# MCU_v14.net
KiCad netlist of a schematic drawn in EAGLE
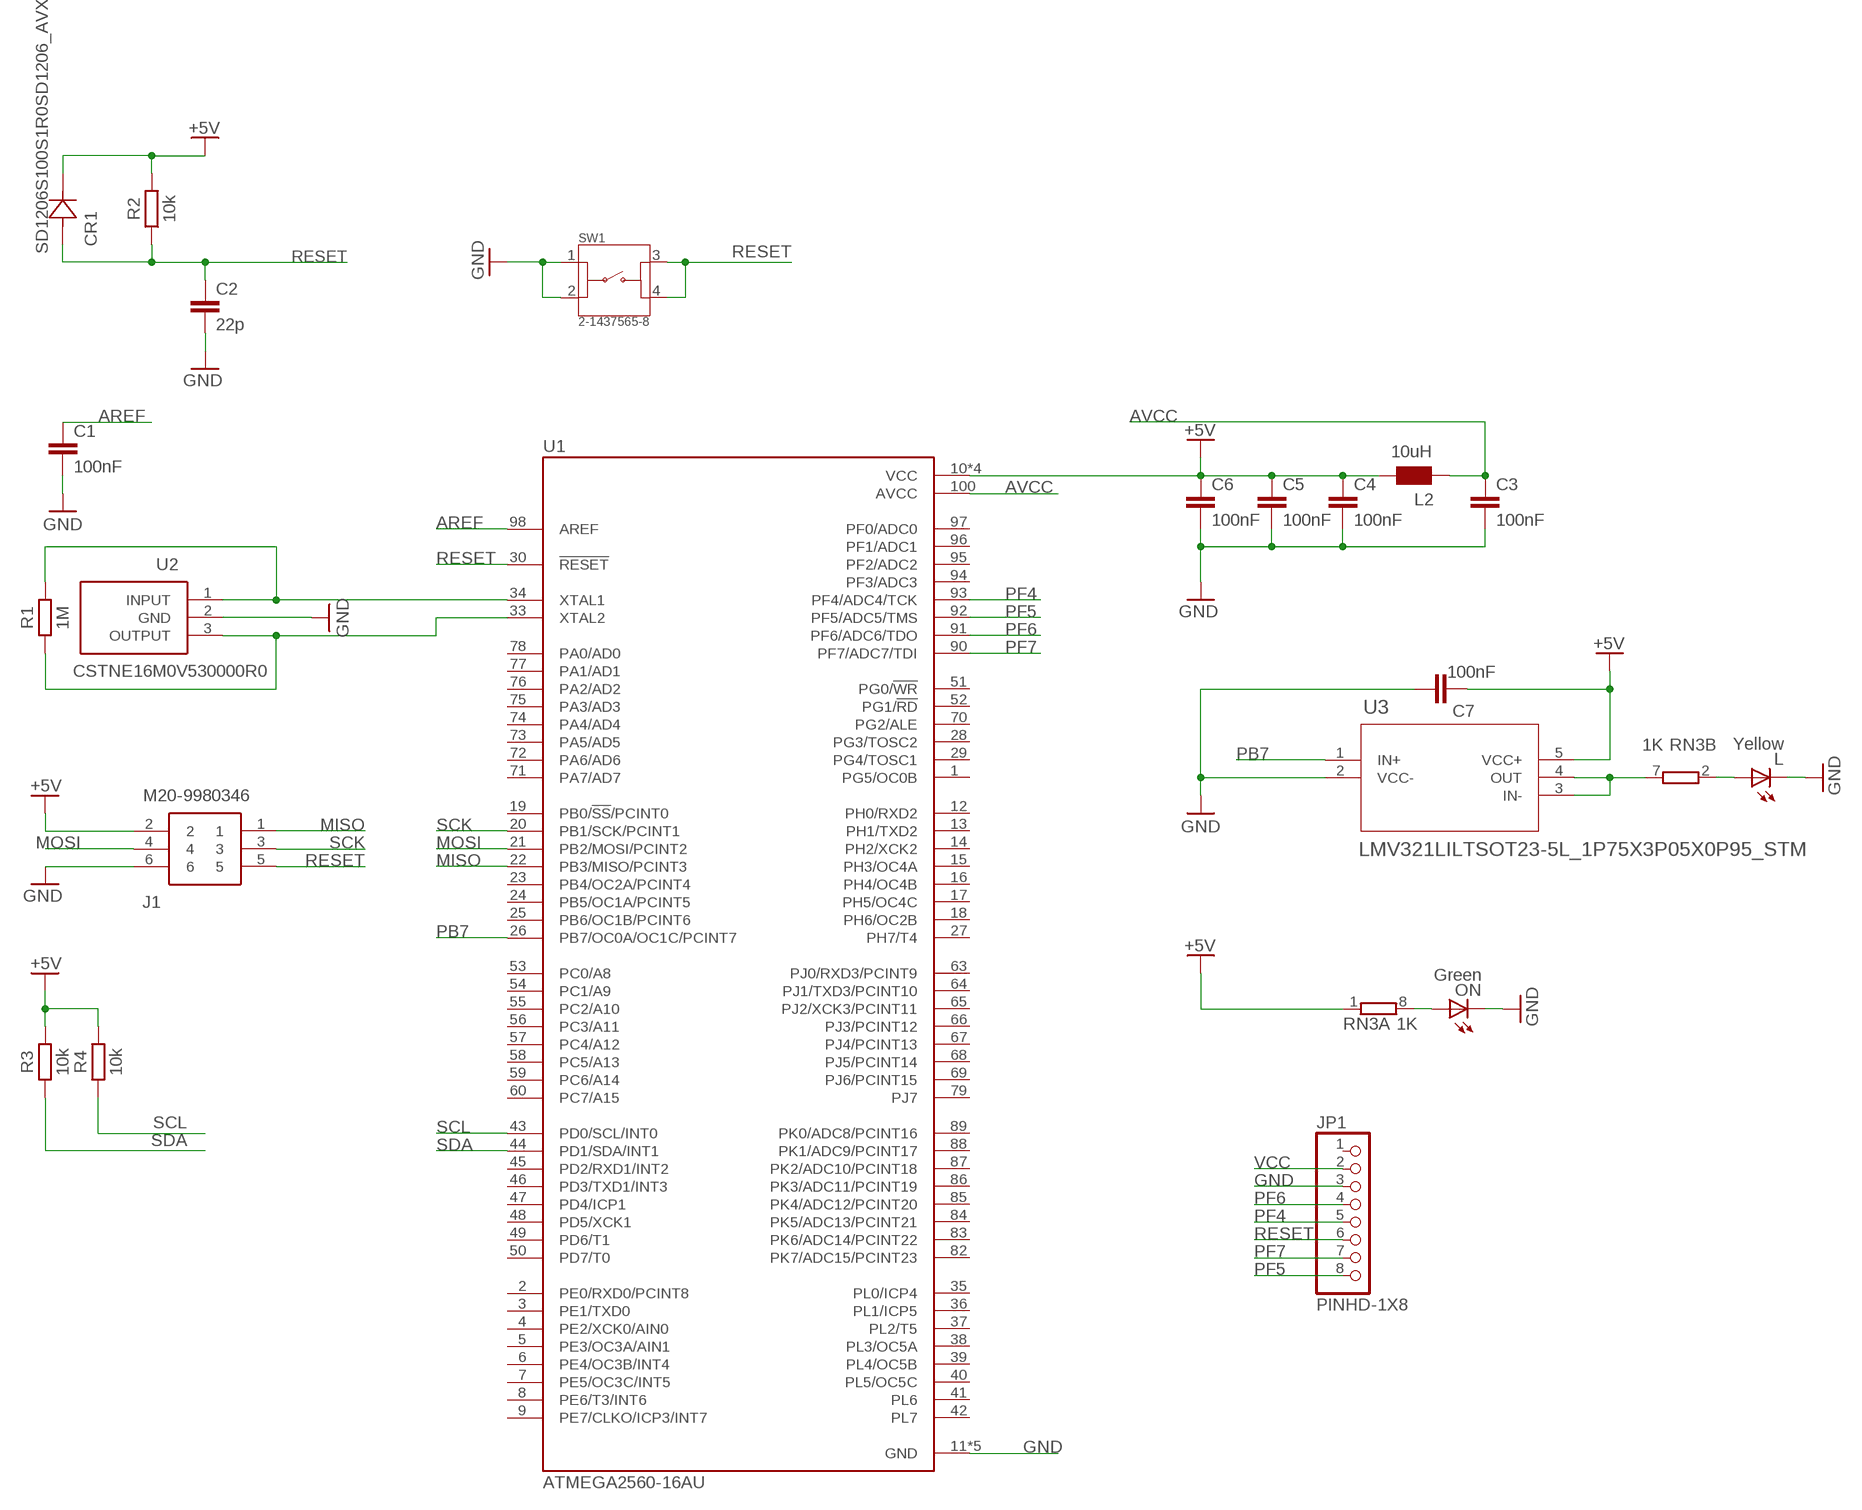
[diagram p0: schematic, sheet 1]

(export (version "E")
  (design (tool "Eeschema 10.0.6"))
  (components
    (comp (ref "C1")
      (value "100nF")
      (footprint "eagle-import:C0603-ROUND")
      (fields (field (name "PART_NUMBER") "cl10b104kbnc"))
      (libsource (lib "eagle-import") (part "0015_100NF_0603"))
    )
    (comp (ref "C2")
      (value "22p")
      (footprint "eagle-import:C0603-ROUND")
      (fields (field (name "PART_NUMBER") "22pF_0603"))
      (libsource (lib "eagle-import") (part "0014_22PF_0603"))
    )
    (comp (ref "C3")
      (value "100nF")
      (footprint "eagle-import:C0603-ROUND")
      (fields (field (name "PART_NUMBER") "cl10b104kbnc"))
      (libsource (lib "eagle-import") (part "0015_100NF_0603"))
    )
    (comp (ref "C4")
      (value "100nF")
      (footprint "eagle-import:C0603-ROUND")
      (fields (field (name "PART_NUMBER") "cl10b104kbnc"))
      (libsource (lib "eagle-import") (part "0015_100NF_0603"))
    )
    (comp (ref "C5")
      (value "100nF")
      (footprint "eagle-import:C0603-ROUND")
      (fields (field (name "PART_NUMBER") "cl10b104kbnc"))
      (libsource (lib "eagle-import") (part "0015_100NF_0603"))
    )
    (comp (ref "C6")
      (value "100nF")
      (footprint "eagle-import:C0603-ROUND")
      (fields (field (name "PART_NUMBER") "cl10b104kbnc"))
      (libsource (lib "eagle-import") (part "0015_100NF_0603"))
    )
    (comp (ref "C7")
      (value "100nF")
      (footprint "eagle-import:C0603-ROUND")
      (fields (field (name "PART_NUMBER") "cl10b104kbnc"))
      (libsource (lib "eagle-import") (part "0015_100NF_0603"))
    )
    (comp (ref "CR1")
      (value "SD1206S100S1R0SD1206_AVX")
      (footprint "eagle-import:SD1206_AVX")
      (fields
        (field (name "MANUFACTURER_PART_NUMBER") "SD1206S100S1R0")
        (field (name "COPYRIGHT") "Copyright (C) 2024 Ultra Librarian. All rights reserved.")
      )
      (libsource (lib "eagle-import") (part "SD1206S100S1R0SD1206_AVX"))
    )
    (comp (ref "J1")
      (value "M20-9980346")
      (footprint "eagle-import:HDRV6W64P254_2X3_762X508X868P")
      (fields (field (name "MOUSER_PART_NUMBER") "855-M20-9980346"))
      (libsource (lib "eagle-import") (part "M20-9980346"))
    )
    (comp (ref "JP1")
      (value "PINHD-1X8")
      (footprint "eagle-import:1X08")
      (fields (field (name "MANUFACTURER") "Generic"))
      (libsource (lib "eagle-import") (part "PINHD-1X8"))
    )
    (comp (ref "L")
      (value "Yellow")
      (footprint "eagle-import:CHIPLED_0805")
      (fields (field (name "PART_NUMBER") "KPT-2012YC"))
      (libsource (lib "eagle-import") (part "0044_KPT-2012YC"))
    )
    (comp (ref "L2")
      (value "10uH")
      (footprint "eagle-import:0805")
      (fields (field (name "PART_NUMBER") "CV201210-100K"))
      (libsource (lib "eagle-import") (part "0715_CV201210-100K"))
    )
    (comp (ref "ON")
      (value "Green")
      (footprint "eagle-import:CHIPLED_0805")
      (fields (field (name "PART_NUMBER") "KPT-2012SGC"))
      (libsource (lib "eagle-import") (part "0043_KPT-2012SGC"))
    )
    (comp (ref "R1")
      (value "1M")
      (footprint "eagle-import:RESC1608X60")
      (libsource (lib "eagle-import") (part "RCHIP-0603(1608-METRIC)_"))
    )
    (comp (ref "R2")
      (value "10k")
      (footprint "eagle-import:RESC2012X65")
      (libsource (lib "eagle-import") (part "RCHIP-0805(2012-METRIC)_"))
    )
    (comp (ref "R3")
      (value "10k")
      (footprint "eagle-import:RESC2012X65")
      (libsource (lib "eagle-import") (part "RCHIP-0805(2012-METRIC)_"))
    )
    (comp (ref "R4")
      (value "10k")
      (footprint "eagle-import:RESC2012X65")
      (libsource (lib "eagle-import") (part "RCHIP-0805(2012-METRIC)_"))
    )
    (comp (ref "RN3")
      (value "1K")
      (footprint "eagle-import:CAY16")
      (fields (field (name "PART_NUMBER") "064R_1K_/_CAY16-102J4LF"))
      (libsource (lib "eagle-import") (part "0005_064R_1K_/_CAY16-102J4LF"))
    )
    (comp (ref "SW1")
      (value "2-1437565-8")
      (footprint "eagle-import:SW_SMD_2-1437565-8_4_4.50_6.00_6.00_5.00")
      (fields (field (name "MANUFACTURER") "TE connectivity"))
      (libsource (lib "eagle-import") (part "2-1437565-8"))
    )
    (comp (ref "U1")
      (value "ATMEGA2560-16AU")
      (footprint "eagle-import:QFP50P1600X1600X120-100N")
      (fields (field (name "MANUFACTURER") "Microchip Technology"))
      (libsource (lib "eagle-import") (part "ATMEGA2560-16AU"))
    )
    (comp (ref "U2")
      (value "CSTNE16M0V530000R0")
      (footprint "eagle-import:CSTNE16M0V530000R0")
      (fields (field (name "MOUSER_PART_NUMBER") "81-CSTNE16M0V530000R"))
      (libsource (lib "eagle-import") (part "CSTNE16M0V530000R0"))
    )
    (comp (ref "U3")
      (value "LMV321LILTSOT23-5L_1P75X3P05X0P95_STM")
      (footprint "eagle-import:SOT23-5L_1P75X3P05X0P95_STM")
      (fields
        (field (name "MANUFACTURER_PART_NUMBER") "LMV321LILT")
        (field (name "COPYRIGHT") "Copyright (C) 2024 Ultra Librarian. All rights reserved.")
      )
      (libsource (lib "eagle-import") (part "LMV321LILTSOT23-5L_1P75X3P05X0P95_STM"))
    )
  )
  (nets
    (net (code "1") (name "+5V") (class "Default")
      (node (ref "C4") (pin "1") (pinfunction "1_1") (pintype "passive"))
      (node (ref "C5") (pin "1") (pinfunction "1_1") (pintype "passive"))
      (node (ref "C6") (pin "1") (pinfunction "1_1") (pintype "passive"))
      (node (ref "C7") (pin "1") (pinfunction "1_1") (pintype "passive"))
      (node (ref "CR1") (pin "1") (pinfunction "1_1") (pintype "passive"))
      (node (ref "J1") (pin "2") (pinfunction "2_2") (pintype "bidirectional"))
      (node (ref "L2") (pin "2") (pinfunction "2_2") (pintype "passive"))
      (node (ref "R2") (pin "2") (pinfunction "2_2") (pintype "passive"))
      (node (ref "R3") (pin "2") (pinfunction "2_2") (pintype "passive"))
      (node (ref "R4") (pin "2") (pinfunction "2_2") (pintype "passive"))
      (node (ref "RN3") (pin "1") (pinfunction "1_1") (pintype "passive"))
      (node (ref "U1") (pin "10") (pinfunction "VCC_10") (pintype "power_in"))
      (node (ref "U1") (pin "31") (pinfunction "VCC_31") (pintype "power_in"))
      (node (ref "U1") (pin "61") (pinfunction "VCC_61") (pintype "power_in"))
      (node (ref "U1") (pin "80") (pinfunction "VCC_80") (pintype "power_in"))
      (node (ref "U3") (pin "5") (pinfunction "VCC+_5") (pintype "power_in"))
    )
    (net (code "2") (name "/AREF") (class "Default")
      (node (ref "C1") (pin "1") (pinfunction "1_1") (pintype "passive"))
      (node (ref "U1") (pin "98") (pinfunction "AREF_98") (pintype "input"))
    )
    (net (code "3") (name "/AVCC") (class "Default")
      (node (ref "C3") (pin "1") (pinfunction "1_1") (pintype "passive"))
      (node (ref "L2") (pin "1") (pinfunction "1_1") (pintype "passive"))
      (node (ref "U1") (pin "100") (pinfunction "AVCC_100") (pintype "power_in"))
    )
    (net (code "4") (name "/MISO") (class "Default")
      (node (ref "J1") (pin "1") (pinfunction "1_1") (pintype "bidirectional"))
      (node (ref "U1") (pin "22") (pinfunction "PB3/MISO/PCINT3_22") (pintype "bidirectional"))
    )
    (net (code "5") (name "/MOSI") (class "Default")
      (node (ref "J1") (pin "4") (pinfunction "4_4") (pintype "bidirectional"))
      (node (ref "U1") (pin "21") (pinfunction "PB2/MOSI/PCINT2_21") (pintype "bidirectional"))
    )
    (net (code "6") (name "/PB7") (class "Default")
      (node (ref "U1") (pin "26") (pinfunction "PB7/OC0A/OC1C/PCINT7_26") (pintype "bidirectional"))
      (node (ref "U3") (pin "1") (pinfunction "IN+_1") (pintype "input"))
    )
    (net (code "7") (name "/PF4") (class "Default")
      (node (ref "JP1") (pin "5") (pinfunction "5_5") (pintype "passive"))
      (node (ref "U1") (pin "93") (pinfunction "PF4/ADC4/TCK_93") (pintype "bidirectional"))
    )
    (net (code "8") (name "/PF5") (class "Default")
      (node (ref "JP1") (pin "8") (pinfunction "8_8") (pintype "passive"))
      (node (ref "U1") (pin "92") (pinfunction "PF5/ADC5/TMS_92") (pintype "bidirectional"))
    )
    (net (code "9") (name "/PF6") (class "Default")
      (node (ref "JP1") (pin "4") (pinfunction "4_4") (pintype "passive"))
      (node (ref "U1") (pin "91") (pinfunction "PF6/ADC6/TDO_91") (pintype "bidirectional"))
    )
    (net (code "10") (name "/PF7") (class "Default")
      (node (ref "JP1") (pin "7") (pinfunction "7_7") (pintype "passive"))
      (node (ref "U1") (pin "90") (pinfunction "PF7/ADC7/TDI_90") (pintype "bidirectional"))
    )
    (net (code "11") (name "/RESET") (class "Default")
      (node (ref "C2") (pin "1") (pinfunction "1_1") (pintype "passive"))
      (node (ref "CR1") (pin "2") (pinfunction "2_2") (pintype "passive"))
      (node (ref "J1") (pin "5") (pinfunction "5_5") (pintype "bidirectional"))
      (node (ref "JP1") (pin "6") (pinfunction "6_6") (pintype "passive"))
      (node (ref "R2") (pin "1") (pinfunction "1_1") (pintype "passive"))
      (node (ref "SW1") (pin "3") (pinfunction "3_3") (pintype "passive"))
      (node (ref "SW1") (pin "4") (pinfunction "4_4") (pintype "passive"))
      (node (ref "U1") (pin "30") (pinfunction "~{RESET}_30") (pintype "input"))
    )
    (net (code "12") (name "/SCK") (class "Default")
      (node (ref "J1") (pin "3") (pinfunction "3_3") (pintype "bidirectional"))
      (node (ref "U1") (pin "20") (pinfunction "PB1/SCK/PCINT1_20") (pintype "bidirectional"))
    )
    (net (code "13") (name "/SCL") (class "Default")
      (node (ref "R4") (pin "1") (pinfunction "1_1") (pintype "passive"))
      (node (ref "U1") (pin "43") (pinfunction "PD0/SCL/INT0_43") (pintype "bidirectional"))
    )
    (net (code "14") (name "/SDA") (class "Default")
      (node (ref "R3") (pin "1") (pinfunction "1_1") (pintype "passive"))
      (node (ref "U1") (pin "44") (pinfunction "PD1/SDA/INT1_44") (pintype "bidirectional"))
    )
    (net (code "15") (name "/VCC") (class "Default")
      (node (ref "JP1") (pin "2") (pinfunction "2_2") (pintype "passive"))
    )
    (net (code "16") (name "GND") (class "Default")
      (node (ref "C1") (pin "2") (pinfunction "2_2") (pintype "passive"))
      (node (ref "C2") (pin "2") (pinfunction "2_2") (pintype "passive"))
      (node (ref "C3") (pin "2") (pinfunction "2_2") (pintype "passive"))
      (node (ref "C4") (pin "2") (pinfunction "2_2") (pintype "passive"))
      (node (ref "C5") (pin "2") (pinfunction "2_2") (pintype "passive"))
      (node (ref "C6") (pin "2") (pinfunction "2_2") (pintype "passive"))
      (node (ref "C7") (pin "2") (pinfunction "2_2") (pintype "passive"))
      (node (ref "J1") (pin "6") (pinfunction "6_6") (pintype "bidirectional"))
      (node (ref "JP1") (pin "3") (pinfunction "3_3") (pintype "passive"))
      (node (ref "L") (pin "C") (pinfunction "C_C") (pintype "passive"))
      (node (ref "ON") (pin "C") (pinfunction "C_C") (pintype "passive"))
      (node (ref "SW1") (pin "1") (pinfunction "1_1") (pintype "passive"))
      (node (ref "SW1") (pin "2") (pinfunction "2_2") (pintype "passive"))
      (node (ref "U1") (pin "11") (pinfunction "GND_11") (pintype "power_in"))
      (node (ref "U1") (pin "32") (pinfunction "GND_32") (pintype "power_in"))
      (node (ref "U1") (pin "62") (pinfunction "GND_62") (pintype "power_in"))
      (node (ref "U1") (pin "81") (pinfunction "GND_81") (pintype "power_in"))
      (node (ref "U1") (pin "99") (pinfunction "GND_99") (pintype "power_in"))
      (node (ref "U2") (pin "2") (pinfunction "GND_2") (pintype "bidirectional"))
      (node (ref "U3") (pin "2") (pinfunction "VCC-_2") (pintype "power_in"))
    )
    (net (code "17") (name "Net-(RN3A-2)") (class "Default")
      (node (ref "ON") (pin "A") (pinfunction "A_A") (pintype "passive"))
      (node (ref "RN3") (pin "8") (pinfunction "2_8") (pintype "passive"))
    )
    (net (code "18") (name "Net-(RN3B-1)") (class "Default")
      (node (ref "L") (pin "A") (pinfunction "A_A") (pintype "passive"))
      (node (ref "RN3") (pin "2") (pinfunction "1_2") (pintype "passive"))
    )
    (net (code "19") (name "Net-(RN3B-2)") (class "Default")
      (node (ref "RN3") (pin "7") (pinfunction "2_7") (pintype "passive"))
      (node (ref "U3") (pin "3") (pinfunction "IN-_3") (pintype "input"))
      (node (ref "U3") (pin "4") (pinfunction "OUT_4") (pintype "output"))
    )
    (net (code "20") (name "Net-(U1-XTAL1)") (class "Default")
      (node (ref "R1") (pin "2") (pinfunction "2_2") (pintype "passive"))
      (node (ref "U1") (pin "34") (pinfunction "XTAL1_34") (pintype "input"))
      (node (ref "U2") (pin "1") (pinfunction "INPUT_1") (pintype "bidirectional"))
    )
    (net (code "21") (name "Net-(U1-XTAL2)") (class "Default")
      (node (ref "R1") (pin "1") (pinfunction "1_1") (pintype "passive"))
      (node (ref "U1") (pin "33") (pinfunction "XTAL2_33") (pintype "output"))
      (node (ref "U2") (pin "3") (pinfunction "OUTPUT_3") (pintype "bidirectional"))
    )
    (net (code "22") (name "unconnected-(JP1-Pad1)") (class "Default")
      (node (ref "JP1") (pin "1") (pinfunction "1_1") (pintype "passive"))
    )
    (net (code "23") (name "unconnected-(U1-PA0{slash}AD0-Pad78)") (class "Default")
      (node (ref "U1") (pin "78") (pinfunction "PA0/AD0_78") (pintype "bidirectional"))
    )
    (net (code "24") (name "unconnected-(U1-PA1{slash}AD1-Pad77)") (class "Default")
      (node (ref "U1") (pin "77") (pinfunction "PA1/AD1_77") (pintype "bidirectional"))
    )
    (net (code "25") (name "unconnected-(U1-PA2{slash}AD2-Pad76)") (class "Default")
      (node (ref "U1") (pin "76") (pinfunction "PA2/AD2_76") (pintype "bidirectional"))
    )
    (net (code "26") (name "unconnected-(U1-PA3{slash}AD3-Pad75)") (class "Default")
      (node (ref "U1") (pin "75") (pinfunction "PA3/AD3_75") (pintype "bidirectional"))
    )
    (net (code "27") (name "unconnected-(U1-PA4{slash}AD4-Pad74)") (class "Default")
      (node (ref "U1") (pin "74") (pinfunction "PA4/AD4_74") (pintype "bidirectional"))
    )
    (net (code "28") (name "unconnected-(U1-PA5{slash}AD5-Pad73)") (class "Default")
      (node (ref "U1") (pin "73") (pinfunction "PA5/AD5_73") (pintype "bidirectional"))
    )
    (net (code "29") (name "unconnected-(U1-PA6{slash}AD6-Pad72)") (class "Default")
      (node (ref "U1") (pin "72") (pinfunction "PA6/AD6_72") (pintype "bidirectional"))
    )
    (net (code "30") (name "unconnected-(U1-PA7{slash}AD7-Pad71)") (class "Default")
      (node (ref "U1") (pin "71") (pinfunction "PA7/AD7_71") (pintype "bidirectional"))
    )
    (net (code "31") (name "unconnected-(U1-PB0{slash}~{SS}{slash}PCINT0-Pad19)") (class "Default")
      (node (ref "U1") (pin "19") (pinfunction "PB0/~{SS}/PCINT0_19") (pintype "bidirectional"))
    )
    (net (code "32") (name "unconnected-(U1-PB4{slash}OC2A{slash}PCINT4-Pad23)") (class "Default")
      (node (ref "U1") (pin "23") (pinfunction "PB4/OC2A/PCINT4_23") (pintype "bidirectional"))
    )
    (net (code "33") (name "unconnected-(U1-PB5{slash}OC1A{slash}PCINT5-Pad24)") (class "Default")
      (node (ref "U1") (pin "24") (pinfunction "PB5/OC1A/PCINT5_24") (pintype "bidirectional"))
    )
    (net (code "34") (name "unconnected-(U1-PB6{slash}OC1B{slash}PCINT6-Pad25)") (class "Default")
      (node (ref "U1") (pin "25") (pinfunction "PB6/OC1B/PCINT6_25") (pintype "bidirectional"))
    )
    (net (code "35") (name "unconnected-(U1-PC0{slash}A8-Pad53)") (class "Default")
      (node (ref "U1") (pin "53") (pinfunction "PC0/A8_53") (pintype "bidirectional"))
    )
    (net (code "36") (name "unconnected-(U1-PC1{slash}A9-Pad54)") (class "Default")
      (node (ref "U1") (pin "54") (pinfunction "PC1/A9_54") (pintype "bidirectional"))
    )
    (net (code "37") (name "unconnected-(U1-PC2{slash}A10-Pad55)") (class "Default")
      (node (ref "U1") (pin "55") (pinfunction "PC2/A10_55") (pintype "bidirectional"))
    )
    (net (code "38") (name "unconnected-(U1-PC3{slash}A11-Pad56)") (class "Default")
      (node (ref "U1") (pin "56") (pinfunction "PC3/A11_56") (pintype "bidirectional"))
    )
    (net (code "39") (name "unconnected-(U1-PC4{slash}A12-Pad57)") (class "Default")
      (node (ref "U1") (pin "57") (pinfunction "PC4/A12_57") (pintype "bidirectional"))
    )
    (net (code "40") (name "unconnected-(U1-PC5{slash}A13-Pad58)") (class "Default")
      (node (ref "U1") (pin "58") (pinfunction "PC5/A13_58") (pintype "bidirectional"))
    )
    (net (code "41") (name "unconnected-(U1-PC6{slash}A14-Pad59)") (class "Default")
      (node (ref "U1") (pin "59") (pinfunction "PC6/A14_59") (pintype "bidirectional"))
    )
    (net (code "42") (name "unconnected-(U1-PC7{slash}A15-Pad60)") (class "Default")
      (node (ref "U1") (pin "60") (pinfunction "PC7/A15_60") (pintype "bidirectional"))
    )
    (net (code "43") (name "unconnected-(U1-PD2{slash}RXD1{slash}INT2-Pad45)") (class "Default")
      (node (ref "U1") (pin "45") (pinfunction "PD2/RXD1/INT2_45") (pintype "bidirectional"))
    )
    (net (code "44") (name "unconnected-(U1-PD3{slash}TXD1{slash}INT3-Pad46)") (class "Default")
      (node (ref "U1") (pin "46") (pinfunction "PD3/TXD1/INT3_46") (pintype "bidirectional"))
    )
    (net (code "45") (name "unconnected-(U1-PD4{slash}ICP1-Pad47)") (class "Default")
      (node (ref "U1") (pin "47") (pinfunction "PD4/ICP1_47") (pintype "bidirectional"))
    )
    (net (code "46") (name "unconnected-(U1-PD5{slash}XCK1-Pad48)") (class "Default")
      (node (ref "U1") (pin "48") (pinfunction "PD5/XCK1_48") (pintype "bidirectional"))
    )
    (net (code "47") (name "unconnected-(U1-PD6{slash}T1-Pad49)") (class "Default")
      (node (ref "U1") (pin "49") (pinfunction "PD6/T1_49") (pintype "bidirectional"))
    )
    (net (code "48") (name "unconnected-(U1-PD7{slash}T0-Pad50)") (class "Default")
      (node (ref "U1") (pin "50") (pinfunction "PD7/T0_50") (pintype "bidirectional"))
    )
    (net (code "49") (name "unconnected-(U1-PE0{slash}RXD0{slash}PCINT8-Pad2)") (class "Default")
      (node (ref "U1") (pin "2") (pinfunction "PE0/RXD0/PCINT8_2") (pintype "bidirectional"))
    )
    (net (code "50") (name "unconnected-(U1-PE1{slash}TXD0-Pad3)") (class "Default")
      (node (ref "U1") (pin "3") (pinfunction "PE1/TXD0_3") (pintype "bidirectional"))
    )
    (net (code "51") (name "unconnected-(U1-PE2{slash}XCK0{slash}AIN0-Pad4)") (class "Default")
      (node (ref "U1") (pin "4") (pinfunction "PE2/XCK0/AIN0_4") (pintype "bidirectional"))
    )
    (net (code "52") (name "unconnected-(U1-PE3{slash}OC3A{slash}AIN1-Pad5)") (class "Default")
      (node (ref "U1") (pin "5") (pinfunction "PE3/OC3A/AIN1_5") (pintype "bidirectional"))
    )
    (net (code "53") (name "unconnected-(U1-PE4{slash}OC3B{slash}INT4-Pad6)") (class "Default")
      (node (ref "U1") (pin "6") (pinfunction "PE4/OC3B/INT4_6") (pintype "bidirectional"))
    )
    (net (code "54") (name "unconnected-(U1-PE5{slash}OC3C{slash}INT5-Pad7)") (class "Default")
      (node (ref "U1") (pin "7") (pinfunction "PE5/OC3C/INT5_7") (pintype "bidirectional"))
    )
    (net (code "55") (name "unconnected-(U1-PE6{slash}T3{slash}INT6-Pad8)") (class "Default")
      (node (ref "U1") (pin "8") (pinfunction "PE6/T3/INT6_8") (pintype "bidirectional"))
    )
    (net (code "56") (name "unconnected-(U1-PE7{slash}CLKO{slash}ICP3{slash}INT7-Pad9)") (class "Default")
      (node (ref "U1") (pin "9") (pinfunction "PE7/CLKO/ICP3/INT7_9") (pintype "bidirectional"))
    )
    (net (code "57") (name "unconnected-(U1-PF0{slash}ADC0-Pad97)") (class "Default")
      (node (ref "U1") (pin "97") (pinfunction "PF0/ADC0_97") (pintype "bidirectional"))
    )
    (net (code "58") (name "unconnected-(U1-PF1{slash}ADC1-Pad96)") (class "Default")
      (node (ref "U1") (pin "96") (pinfunction "PF1/ADC1_96") (pintype "bidirectional"))
    )
    (net (code "59") (name "unconnected-(U1-PF2{slash}ADC2-Pad95)") (class "Default")
      (node (ref "U1") (pin "95") (pinfunction "PF2/ADC2_95") (pintype "bidirectional"))
    )
    (net (code "60") (name "unconnected-(U1-PF3{slash}ADC3-Pad94)") (class "Default")
      (node (ref "U1") (pin "94") (pinfunction "PF3/ADC3_94") (pintype "bidirectional"))
    )
    (net (code "61") (name "unconnected-(U1-PG0{slash}~{WR}-Pad51)") (class "Default")
      (node (ref "U1") (pin "51") (pinfunction "PG0/~{WR}_51") (pintype "bidirectional"))
    )
    (net (code "62") (name "unconnected-(U1-PG1{slash}~{RD}-Pad52)") (class "Default")
      (node (ref "U1") (pin "52") (pinfunction "PG1/~{RD}_52") (pintype "bidirectional"))
    )
    (net (code "63") (name "unconnected-(U1-PG2{slash}ALE-Pad70)") (class "Default")
      (node (ref "U1") (pin "70") (pinfunction "PG2/ALE_70") (pintype "bidirectional"))
    )
    (net (code "64") (name "unconnected-(U1-PG3{slash}TOSC2-Pad28)") (class "Default")
      (node (ref "U1") (pin "28") (pinfunction "PG3/TOSC2_28") (pintype "bidirectional"))
    )
    (net (code "65") (name "unconnected-(U1-PG4{slash}TOSC1-Pad29)") (class "Default")
      (node (ref "U1") (pin "29") (pinfunction "PG4/TOSC1_29") (pintype "bidirectional"))
    )
    (net (code "66") (name "unconnected-(U1-PG5{slash}OC0B-Pad1)") (class "Default")
      (node (ref "U1") (pin "1") (pinfunction "PG5/OC0B_1") (pintype "bidirectional"))
    )
    (net (code "67") (name "unconnected-(U1-PH0{slash}RXD2-Pad12)") (class "Default")
      (node (ref "U1") (pin "12") (pinfunction "PH0/RXD2_12") (pintype "bidirectional"))
    )
    (net (code "68") (name "unconnected-(U1-PH1{slash}TXD2-Pad13)") (class "Default")
      (node (ref "U1") (pin "13") (pinfunction "PH1/TXD2_13") (pintype "bidirectional"))
    )
    (net (code "69") (name "unconnected-(U1-PH2{slash}XCK2-Pad14)") (class "Default")
      (node (ref "U1") (pin "14") (pinfunction "PH2/XCK2_14") (pintype "bidirectional"))
    )
    (net (code "70") (name "unconnected-(U1-PH3{slash}OC4A-Pad15)") (class "Default")
      (node (ref "U1") (pin "15") (pinfunction "PH3/OC4A_15") (pintype "bidirectional"))
    )
    (net (code "71") (name "unconnected-(U1-PH4{slash}OC4B-Pad16)") (class "Default")
      (node (ref "U1") (pin "16") (pinfunction "PH4/OC4B_16") (pintype "bidirectional"))
    )
    (net (code "72") (name "unconnected-(U1-PH5{slash}OC4C-Pad17)") (class "Default")
      (node (ref "U1") (pin "17") (pinfunction "PH5/OC4C_17") (pintype "bidirectional"))
    )
    (net (code "73") (name "unconnected-(U1-PH6{slash}OC2B-Pad18)") (class "Default")
      (node (ref "U1") (pin "18") (pinfunction "PH6/OC2B_18") (pintype "bidirectional"))
    )
    (net (code "74") (name "unconnected-(U1-PH7{slash}T4-Pad27)") (class "Default")
      (node (ref "U1") (pin "27") (pinfunction "PH7/T4_27") (pintype "bidirectional"))
    )
    (net (code "75") (name "unconnected-(U1-PJ0{slash}RXD3{slash}PCINT9-Pad63)") (class "Default")
      (node (ref "U1") (pin "63") (pinfunction "PJ0/RXD3/PCINT9_63") (pintype "bidirectional"))
    )
    (net (code "76") (name "unconnected-(U1-PJ1{slash}TXD3{slash}PCINT10-Pad64)") (class "Default")
      (node (ref "U1") (pin "64") (pinfunction "PJ1/TXD3/PCINT10_64") (pintype "bidirectional"))
    )
    (net (code "77") (name "unconnected-(U1-PJ2{slash}XCK3{slash}PCINT11-Pad65)") (class "Default")
      (node (ref "U1") (pin "65") (pinfunction "PJ2/XCK3/PCINT11_65") (pintype "bidirectional"))
    )
    (net (code "78") (name "unconnected-(U1-PJ3{slash}PCINT12-Pad66)") (class "Default")
      (node (ref "U1") (pin "66") (pinfunction "PJ3/PCINT12_66") (pintype "bidirectional"))
    )
    (net (code "79") (name "unconnected-(U1-PJ4{slash}PCINT13-Pad67)") (class "Default")
      (node (ref "U1") (pin "67") (pinfunction "PJ4/PCINT13_67") (pintype "bidirectional"))
    )
    (net (code "80") (name "unconnected-(U1-PJ5{slash}PCINT14-Pad68)") (class "Default")
      (node (ref "U1") (pin "68") (pinfunction "PJ5/PCINT14_68") (pintype "bidirectional"))
    )
    (net (code "81") (name "unconnected-(U1-PJ6{slash}PCINT15-Pad69)") (class "Default")
      (node (ref "U1") (pin "69") (pinfunction "PJ6/PCINT15_69") (pintype "bidirectional"))
    )
    (net (code "82") (name "unconnected-(U1-PJ7-Pad79)") (class "Default")
      (node (ref "U1") (pin "79") (pinfunction "PJ7_79") (pintype "bidirectional"))
    )
    (net (code "83") (name "unconnected-(U1-PK0{slash}ADC8{slash}PCINT16-Pad89)") (class "Default")
      (node (ref "U1") (pin "89") (pinfunction "PK0/ADC8/PCINT16_89") (pintype "bidirectional"))
    )
    (net (code "84") (name "unconnected-(U1-PK1{slash}ADC9{slash}PCINT17-Pad88)") (class "Default")
      (node (ref "U1") (pin "88") (pinfunction "PK1/ADC9/PCINT17_88") (pintype "bidirectional"))
    )
    (net (code "85") (name "unconnected-(U1-PK2{slash}ADC10{slash}PCINT18-Pad87)") (class "Default")
      (node (ref "U1") (pin "87") (pinfunction "PK2/ADC10/PCINT18_87") (pintype "bidirectional"))
    )
    (net (code "86") (name "unconnected-(U1-PK3{slash}ADC11{slash}PCINT19-Pad86)") (class "Default")
      (node (ref "U1") (pin "86") (pinfunction "PK3/ADC11/PCINT19_86") (pintype "bidirectional"))
    )
    (net (code "87") (name "unconnected-(U1-PK4{slash}ADC12{slash}PCINT20-Pad85)") (class "Default")
      (node (ref "U1") (pin "85") (pinfunction "PK4/ADC12/PCINT20_85") (pintype "bidirectional"))
    )
    (net (code "88") (name "unconnected-(U1-PK5{slash}ADC13{slash}PCINT21-Pad84)") (class "Default")
      (node (ref "U1") (pin "84") (pinfunction "PK5/ADC13/PCINT21_84") (pintype "bidirectional"))
    )
    (net (code "89") (name "unconnected-(U1-PK6{slash}ADC14{slash}PCINT22-Pad83)") (class "Default")
      (node (ref "U1") (pin "83") (pinfunction "PK6/ADC14/PCINT22_83") (pintype "bidirectional"))
    )
    (net (code "90") (name "unconnected-(U1-PK7{slash}ADC15{slash}PCINT23-Pad82)") (class "Default")
      (node (ref "U1") (pin "82") (pinfunction "PK7/ADC15/PCINT23_82") (pintype "bidirectional"))
    )
    (net (code "91") (name "unconnected-(U1-PL0{slash}ICP4-Pad35)") (class "Default")
      (node (ref "U1") (pin "35") (pinfunction "PL0/ICP4_35") (pintype "bidirectional"))
    )
    (net (code "92") (name "unconnected-(U1-PL1{slash}ICP5-Pad36)") (class "Default")
      (node (ref "U1") (pin "36") (pinfunction "PL1/ICP5_36") (pintype "bidirectional"))
    )
    (net (code "93") (name "unconnected-(U1-PL2{slash}T5-Pad37)") (class "Default")
      (node (ref "U1") (pin "37") (pinfunction "PL2/T5_37") (pintype "bidirectional"))
    )
    (net (code "94") (name "unconnected-(U1-PL3{slash}OC5A-Pad38)") (class "Default")
      (node (ref "U1") (pin "38") (pinfunction "PL3/OC5A_38") (pintype "bidirectional"))
    )
    (net (code "95") (name "unconnected-(U1-PL4{slash}OC5B-Pad39)") (class "Default")
      (node (ref "U1") (pin "39") (pinfunction "PL4/OC5B_39") (pintype "bidirectional"))
    )
    (net (code "96") (name "unconnected-(U1-PL5{slash}OC5C-Pad40)") (class "Default")
      (node (ref "U1") (pin "40") (pinfunction "PL5/OC5C_40") (pintype "bidirectional"))
    )
    (net (code "97") (name "unconnected-(U1-PL6-Pad41)") (class "Default")
      (node (ref "U1") (pin "41") (pinfunction "PL6_41") (pintype "bidirectional"))
    )
    (net (code "98") (name "unconnected-(U1-PL7-Pad42)") (class "Default")
      (node (ref "U1") (pin "42") (pinfunction "PL7_42") (pintype "bidirectional"))
    )
  )
)
